# pinoccio-4x1a-motor.net
KiCad netlist of a schematic drawn in EAGLE
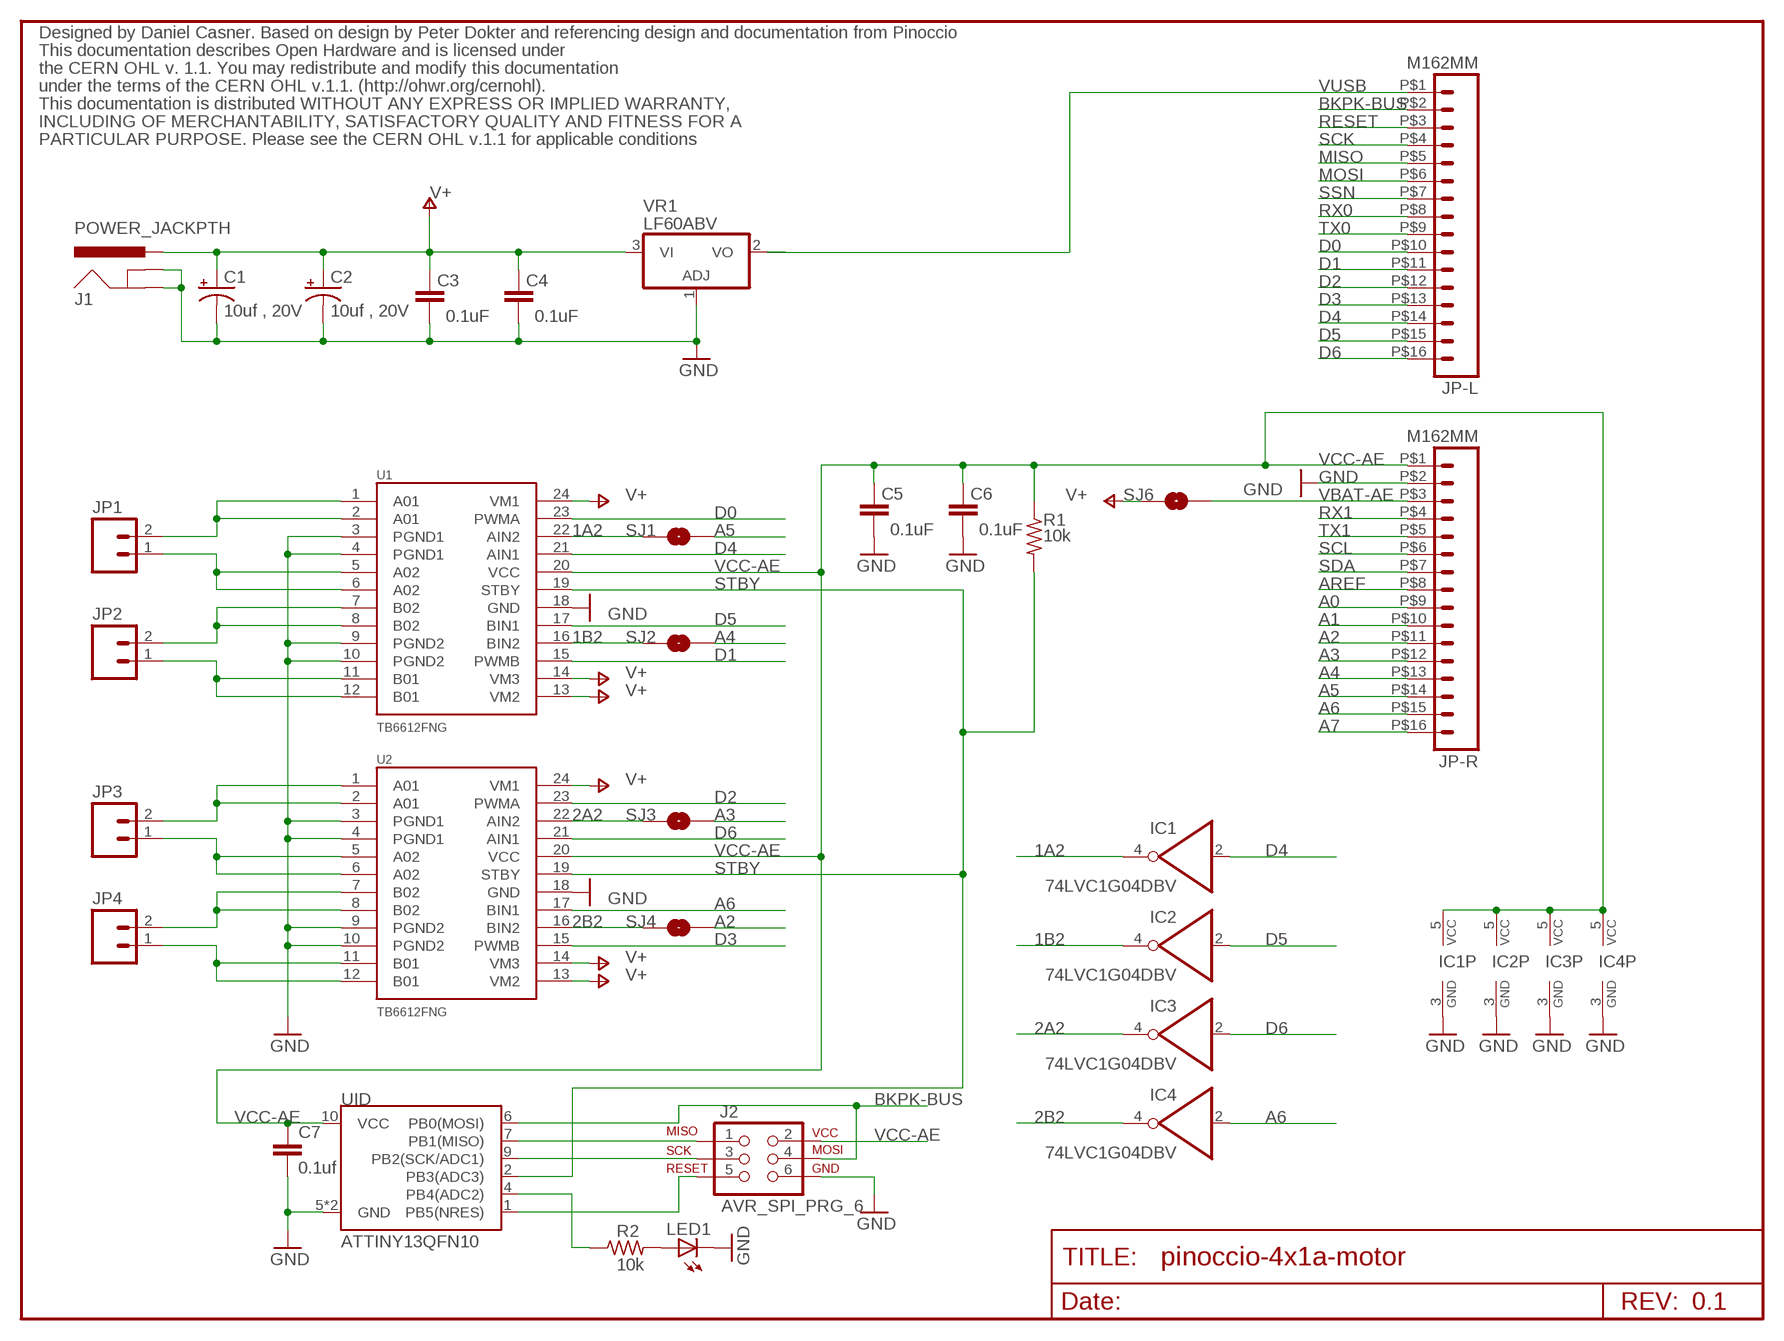
[diagram p0: schematic, sheet 1]

(export (version "E")
  (design (tool "Eeschema 10.0.6"))
  (components
    (comp (ref "C1")
      (value "10uf , 20V")
      (footprint "eagle-import:EIA3528")
      (libsource (lib "eagle-import") (part "CAP_POL3528"))
    )
    (comp (ref "C2")
      (value "10uf , 20V")
      (footprint "eagle-import:EIA3528")
      (libsource (lib "eagle-import") (part "CAP_POL3528"))
    )
    (comp (ref "C3")
      (value "0.1uF")
      (footprint "eagle-import:0402-CAP")
      (libsource (lib "eagle-import") (part "SparkFun_CAP0402-CAP"))
    )
    (comp (ref "C4")
      (value "0.1uF")
      (footprint "eagle-import:0402-CAP")
      (libsource (lib "eagle-import") (part "SparkFun_CAP0402-CAP"))
    )
    (comp (ref "C5")
      (value "0.1uF")
      (footprint "eagle-import:0402-CAP")
      (libsource (lib "eagle-import") (part "SparkFun_CAP0402-CAP"))
    )
    (comp (ref "C6")
      (value "0.1uF")
      (footprint "eagle-import:0402-CAP")
      (libsource (lib "eagle-import") (part "SparkFun_CAP0402-CAP"))
    )
    (comp (ref "C7")
      (value "0.1uf")
      (footprint "eagle-import:0402-CAP")
      (libsource (lib "eagle-import") (part "CAP0402-CAP"))
    )
    (comp (ref "IC1")
      (value "74LVC1G04DBV")
      (footprint "eagle-import:SOT23-5")
      (libsource (lib "eagle-import") (part "741G04DBVLVC"))
    )
    (comp (ref "IC2")
      (value "74LVC1G04DBV")
      (footprint "eagle-import:SOT23-5")
      (libsource (lib "eagle-import") (part "741G04DBVLVC"))
    )
    (comp (ref "IC3")
      (value "74LVC1G04DBV")
      (footprint "eagle-import:SOT23-5")
      (libsource (lib "eagle-import") (part "741G04DBVLVC"))
    )
    (comp (ref "IC4")
      (value "74LVC1G04DBV")
      (footprint "eagle-import:SOT23-5")
      (libsource (lib "eagle-import") (part "741G04DBVLVC"))
    )
    (comp (ref "J1")
      (value "POWER_JACKPTH")
      (footprint "eagle-import:POWER_JACK_PTH")
      (libsource (lib "eagle-import") (part "POWER_JACKPTH"))
    )
    (comp (ref "J2")
      (value "AVR_SPI_PRG_6")
      (footprint "eagle-import:2X3-PAD")
      (libsource (lib "eagle-import") (part "AVR_SPI_PRG_6"))
    )
    (comp (ref "JP-L")
      (value "M162MM")
      (footprint "eagle-import:1X16_2MM")
      (libsource (lib "eagle-import") (part "M162MM"))
    )
    (comp (ref "JP-R")
      (value "M162MM")
      (footprint "eagle-import:1X16_2MM")
      (libsource (lib "eagle-import") (part "M162MM"))
    )
    (comp (ref "JP1")
      (value "M02LOCK_LONGPADS")
      (footprint "eagle-import:1X02_LOCK_LONGPADS")
      (libsource (lib "eagle-import") (part "M02LOCK_LONGPADS"))
    )
    (comp (ref "JP2")
      (value "M02LOCK_LONGPADS")
      (footprint "eagle-import:1X02_LOCK_LONGPADS")
      (libsource (lib "eagle-import") (part "M02LOCK_LONGPADS"))
    )
    (comp (ref "JP3")
      (value "M02LOCK_LONGPADS")
      (footprint "eagle-import:1X02_LOCK_LONGPADS")
      (libsource (lib "eagle-import") (part "M02LOCK_LONGPADS"))
    )
    (comp (ref "JP4")
      (value "M02LOCK_LONGPADS")
      (footprint "eagle-import:1X02_LOCK_LONGPADS")
      (libsource (lib "eagle-import") (part "M02LOCK_LONGPADS"))
    )
    (comp (ref "LED1")
      (value "LED0603")
      (footprint "eagle-import:LED-0603")
      (libsource (lib "eagle-import") (part "LED0603"))
    )
    (comp (ref "R1")
      (value "10k")
      (footprint "eagle-import:R0402")
      (libsource (lib "eagle-import") (part "R-US_R0402"))
    )
    (comp (ref "R2")
      (value "10k")
      (footprint "eagle-import:R0402")
      (libsource (lib "eagle-import") (part "R-US_R0402"))
    )
    (comp (ref "SJ1")
      (value "SOLDERJUMPERNC2")
      (footprint "eagle-import:SJ_2S-NOTRACE")
      (libsource (lib "eagle-import") (part "SOLDERJUMPERNC2"))
    )
    (comp (ref "SJ2")
      (value "SOLDERJUMPERNC2")
      (footprint "eagle-import:SJ_2S-NOTRACE")
      (libsource (lib "eagle-import") (part "SOLDERJUMPERNC2"))
    )
    (comp (ref "SJ3")
      (value "SOLDERJUMPERNC2")
      (footprint "eagle-import:SJ_2S-NOTRACE")
      (libsource (lib "eagle-import") (part "SOLDERJUMPERNC2"))
    )
    (comp (ref "SJ4")
      (value "SOLDERJUMPERNC2")
      (footprint "eagle-import:SJ_2S-NOTRACE")
      (libsource (lib "eagle-import") (part "SOLDERJUMPERNC2"))
    )
    (comp (ref "SJ6")
      (value "SOLDERJUMPERNC2")
      (footprint "eagle-import:SJ_2S-NOTRACE")
      (libsource (lib "eagle-import") (part "SOLDERJUMPERNC2"))
    )
    (comp (ref "U1")
      (value "TB6612FNG")
      (footprint "eagle-import:SSOP24")
      (libsource (lib "eagle-import") (part "TB6621FNG"))
    )
    (comp (ref "U2")
      (value "TB6612FNG")
      (footprint "eagle-import:SSOP24")
      (libsource (lib "eagle-import") (part "TB6621FNG"))
    )
    (comp (ref "UID")
      (value "ATTINY13QFN10")
      (footprint "eagle-import:QFN-10")
      (libsource (lib "eagle-import") (part "ATTINY13QFN10"))
    )
    (comp (ref "VR1")
      (value "LF60ABV")
      (footprint "eagle-import:TO220H")
      (libsource (lib "eagle-import") (part "317T"))
    )
  )
  (nets
    (net (code "1") (name "/1A2") (class "Default")
      (node (ref "IC1") (pin "4") (pinfunction "O_4") (pintype "output"))
      (node (ref "SJ1") (pin "1") (pinfunction "1_1") (pintype "passive"))
      (node (ref "U1") (pin "22") (pinfunction "AIN2_22") (pintype "bidirectional"))
    )
    (net (code "2") (name "/1B2") (class "Default")
      (node (ref "IC2") (pin "4") (pinfunction "O_4") (pintype "output"))
      (node (ref "SJ2") (pin "1") (pinfunction "1_1") (pintype "passive"))
      (node (ref "U1") (pin "16") (pinfunction "BIN2_16") (pintype "bidirectional"))
    )
    (net (code "3") (name "/2A2") (class "Default")
      (node (ref "IC3") (pin "4") (pinfunction "O_4") (pintype "output"))
      (node (ref "SJ3") (pin "1") (pinfunction "1_1") (pintype "passive"))
      (node (ref "U2") (pin "22") (pinfunction "AIN2_22") (pintype "bidirectional"))
    )
    (net (code "4") (name "/2B2") (class "Default")
      (node (ref "IC4") (pin "4") (pinfunction "O_4") (pintype "output"))
      (node (ref "SJ4") (pin "1") (pinfunction "1_1") (pintype "passive"))
      (node (ref "U2") (pin "16") (pinfunction "BIN2_16") (pintype "bidirectional"))
    )
    (net (code "5") (name "/A0") (class "Default")
      (node (ref "JP-R") (pin "P$9") (pinfunction "9_P$9") (pintype "passive"))
    )
    (net (code "6") (name "/A1") (class "Default")
      (node (ref "JP-R") (pin "P$10") (pinfunction "10_P$10") (pintype "passive"))
    )
    (net (code "7") (name "/A2") (class "Default")
      (node (ref "JP-R") (pin "P$11") (pinfunction "11_P$11") (pintype "passive"))
      (node (ref "SJ4") (pin "2") (pinfunction "2_2") (pintype "passive"))
    )
    (net (code "8") (name "/A3") (class "Default")
      (node (ref "JP-R") (pin "P$12") (pinfunction "12_P$12") (pintype "passive"))
      (node (ref "SJ3") (pin "2") (pinfunction "2_2") (pintype "passive"))
    )
    (net (code "9") (name "/A4") (class "Default")
      (node (ref "JP-R") (pin "P$13") (pinfunction "13_P$13") (pintype "passive"))
      (node (ref "SJ2") (pin "2") (pinfunction "2_2") (pintype "passive"))
    )
    (net (code "10") (name "/A5") (class "Default")
      (node (ref "JP-R") (pin "P$14") (pinfunction "14_P$14") (pintype "passive"))
      (node (ref "SJ1") (pin "2") (pinfunction "2_2") (pintype "passive"))
    )
    (net (code "11") (name "/A6") (class "Default")
      (node (ref "IC4") (pin "2") (pinfunction "I_2") (pintype "input"))
      (node (ref "JP-R") (pin "P$15") (pinfunction "15_P$15") (pintype "passive"))
      (node (ref "U2") (pin "17") (pinfunction "BIN1_17") (pintype "bidirectional"))
    )
    (net (code "12") (name "/A7") (class "Default")
      (node (ref "JP-R") (pin "P$16") (pinfunction "16_P$16") (pintype "passive"))
    )
    (net (code "13") (name "/AREF") (class "Default")
      (node (ref "JP-R") (pin "P$8") (pinfunction "8_P$8") (pintype "passive"))
    )
    (net (code "14") (name "/BKPK-BUS") (class "Default")
      (node (ref "J2") (pin "4") (pinfunction "4_4") (pintype "passive"))
      (node (ref "JP-L") (pin "P$2") (pinfunction "2_P$2") (pintype "passive"))
      (node (ref "UID") (pin "6") (pinfunction "PB0(MOSI)_6") (pintype "bidirectional"))
    )
    (net (code "15") (name "/D0") (class "Default")
      (node (ref "JP-L") (pin "P$10") (pinfunction "10_P$10") (pintype "passive"))
      (node (ref "U1") (pin "23") (pinfunction "PWMA_23") (pintype "bidirectional"))
    )
    (net (code "16") (name "/D1") (class "Default")
      (node (ref "JP-L") (pin "P$11") (pinfunction "11_P$11") (pintype "passive"))
      (node (ref "U1") (pin "15") (pinfunction "PWMB_15") (pintype "bidirectional"))
    )
    (net (code "17") (name "/D2") (class "Default")
      (node (ref "JP-L") (pin "P$12") (pinfunction "12_P$12") (pintype "passive"))
      (node (ref "U2") (pin "23") (pinfunction "PWMA_23") (pintype "bidirectional"))
    )
    (net (code "18") (name "/D3") (class "Default")
      (node (ref "JP-L") (pin "P$13") (pinfunction "13_P$13") (pintype "passive"))
      (node (ref "U2") (pin "15") (pinfunction "PWMB_15") (pintype "bidirectional"))
    )
    (net (code "19") (name "/D4") (class "Default")
      (node (ref "IC1") (pin "2") (pinfunction "I_2") (pintype "input"))
      (node (ref "JP-L") (pin "P$14") (pinfunction "14_P$14") (pintype "passive"))
      (node (ref "U1") (pin "21") (pinfunction "AIN1_21") (pintype "bidirectional"))
    )
    (net (code "20") (name "/D5") (class "Default")
      (node (ref "IC2") (pin "2") (pinfunction "I_2") (pintype "input"))
      (node (ref "JP-L") (pin "P$15") (pinfunction "15_P$15") (pintype "passive"))
      (node (ref "U1") (pin "17") (pinfunction "BIN1_17") (pintype "bidirectional"))
    )
    (net (code "21") (name "/D6") (class "Default")
      (node (ref "IC3") (pin "2") (pinfunction "I_2") (pintype "input"))
      (node (ref "JP-L") (pin "P$16") (pinfunction "16_P$16") (pintype "passive"))
      (node (ref "U2") (pin "21") (pinfunction "AIN1_21") (pintype "bidirectional"))
    )
    (net (code "22") (name "/MISO") (class "Default")
      (node (ref "JP-L") (pin "P$5") (pinfunction "5_P$5") (pintype "passive"))
    )
    (net (code "23") (name "/MOSI") (class "Default")
      (node (ref "JP-L") (pin "P$6") (pinfunction "6_P$6") (pintype "passive"))
    )
    (net (code "24") (name "/RESET") (class "Default")
      (node (ref "JP-L") (pin "P$3") (pinfunction "3_P$3") (pintype "passive"))
    )
    (net (code "25") (name "/RX0") (class "Default")
      (node (ref "JP-L") (pin "P$8") (pinfunction "8_P$8") (pintype "passive"))
    )
    (net (code "26") (name "/RX1") (class "Default")
      (node (ref "JP-R") (pin "P$4") (pinfunction "4_P$4") (pintype "passive"))
    )
    (net (code "27") (name "/SCK") (class "Default")
      (node (ref "JP-L") (pin "P$4") (pinfunction "4_P$4") (pintype "passive"))
    )
    (net (code "28") (name "/SCL") (class "Default")
      (node (ref "JP-R") (pin "P$6") (pinfunction "6_P$6") (pintype "passive"))
    )
    (net (code "29") (name "/SDA") (class "Default")
      (node (ref "JP-R") (pin "P$7") (pinfunction "7_P$7") (pintype "passive"))
    )
    (net (code "30") (name "/SSN") (class "Default")
      (node (ref "JP-L") (pin "P$7") (pinfunction "7_P$7") (pintype "passive"))
    )
    (net (code "31") (name "/STBY") (class "Default")
      (node (ref "R1") (pin "2") (pinfunction "2_2") (pintype "passive"))
      (node (ref "U1") (pin "19") (pinfunction "STBY_19") (pintype "bidirectional"))
      (node (ref "U2") (pin "19") (pinfunction "STBY_19") (pintype "bidirectional"))
      (node (ref "UID") (pin "2") (pinfunction "PB3(ADC3)_2") (pintype "bidirectional"))
    )
    (net (code "32") (name "/TX0") (class "Default")
      (node (ref "JP-L") (pin "P$9") (pinfunction "9_P$9") (pintype "passive"))
    )
    (net (code "33") (name "/TX1") (class "Default")
      (node (ref "JP-R") (pin "P$5") (pinfunction "5_P$5") (pintype "passive"))
    )
    (net (code "34") (name "/VBAT-AE") (class "Default")
      (node (ref "JP-R") (pin "P$3") (pinfunction "3_P$3") (pintype "passive"))
      (node (ref "SJ6") (pin "2") (pinfunction "2_2") (pintype "passive"))
    )
    (net (code "35") (name "/VCC-AE") (class "Default")
      (node (ref "C5") (pin "2") (pinfunction "2_2") (pintype "passive"))
      (node (ref "C6") (pin "2") (pinfunction "2_2") (pintype "passive"))
      (node (ref "C7") (pin "1") (pinfunction "1_1") (pintype "passive"))
      (node (ref "IC1") (pin "5") (pinfunction "VCC_5") (pintype "power_in"))
      (node (ref "IC2") (pin "5") (pinfunction "VCC_5") (pintype "power_in"))
      (node (ref "IC3") (pin "5") (pinfunction "VCC_5") (pintype "power_in"))
      (node (ref "IC4") (pin "5") (pinfunction "VCC_5") (pintype "power_in"))
      (node (ref "J2") (pin "2") (pinfunction "2_2") (pintype "passive"))
      (node (ref "JP-R") (pin "P$1") (pinfunction "1_P$1") (pintype "passive"))
      (node (ref "R1") (pin "1") (pinfunction "1_1") (pintype "passive"))
      (node (ref "U1") (pin "20") (pinfunction "VCC_20") (pintype "bidirectional"))
      (node (ref "U2") (pin "20") (pinfunction "VCC_20") (pintype "bidirectional"))
      (node (ref "UID") (pin "10") (pinfunction "VCC_10") (pintype "bidirectional"))
    )
    (net (code "36") (name "/VUSB") (class "Default")
      (node (ref "JP-L") (pin "P$1") (pinfunction "1_P$1") (pintype "passive"))
      (node (ref "VR1") (pin "2") (pinfunction "VO_2") (pintype "passive"))
    )
    (net (code "37") (name "GND") (class "Default")
      (node (ref "C1") (pin "C") (pinfunction "-_C") (pintype "passive"))
      (node (ref "C2") (pin "C") (pinfunction "-_C") (pintype "passive"))
      (node (ref "C3") (pin "1") (pinfunction "1_1") (pintype "passive"))
      (node (ref "C4") (pin "1") (pinfunction "1_1") (pintype "passive"))
      (node (ref "C5") (pin "1") (pinfunction "1_1") (pintype "passive"))
      (node (ref "C6") (pin "1") (pinfunction "1_1") (pintype "passive"))
      (node (ref "C7") (pin "2") (pinfunction "2_2") (pintype "passive"))
      (node (ref "IC1") (pin "3") (pinfunction "GND_3") (pintype "power_in"))
      (node (ref "IC2") (pin "3") (pinfunction "GND_3") (pintype "power_in"))
      (node (ref "IC3") (pin "3") (pinfunction "GND_3") (pintype "power_in"))
      (node (ref "IC4") (pin "3") (pinfunction "GND_3") (pintype "power_in"))
      (node (ref "J1") (pin "GND") (pinfunction "GND_GND") (pintype "bidirectional"))
      (node (ref "J1") (pin "GNDBREAK") (pinfunction "GNDBREAK_GNDBREAK") (pintype "bidirectional"))
      (node (ref "J2") (pin "6") (pinfunction "6_6") (pintype "passive"))
      (node (ref "JP-R") (pin "P$2") (pinfunction "2_P$2") (pintype "passive"))
      (node (ref "LED1") (pin "C") (pinfunction "C_C") (pintype "passive"))
      (node (ref "U1") (pin "10") (pinfunction "PGND2_10") (pintype "bidirectional"))
      (node (ref "U1") (pin "18") (pinfunction "GND_18") (pintype "bidirectional"))
      (node (ref "U1") (pin "3") (pinfunction "PGND1_3") (pintype "bidirectional"))
      (node (ref "U1") (pin "4") (pinfunction "PGND1_4") (pintype "bidirectional"))
      (node (ref "U1") (pin "9") (pinfunction "PGND2_9") (pintype "bidirectional"))
      (node (ref "U2") (pin "10") (pinfunction "PGND2_10") (pintype "bidirectional"))
      (node (ref "U2") (pin "18") (pinfunction "GND_18") (pintype "bidirectional"))
      (node (ref "U2") (pin "3") (pinfunction "PGND1_3") (pintype "bidirectional"))
      (node (ref "U2") (pin "4") (pinfunction "PGND1_4") (pintype "bidirectional"))
      (node (ref "U2") (pin "9") (pinfunction "PGND2_9") (pintype "bidirectional"))
      (node (ref "UID") (pin "5") (pinfunction "GND_5") (pintype "bidirectional"))
      (node (ref "UID") (pin "EP") (pinfunction "GND_EP") (pintype "bidirectional"))
      (node (ref "VR1") (pin "1") (pinfunction "ADJ_1") (pintype "input"))
    )
    (net (code "38") (name "Net-(JP1-Pad1)") (class "Default")
      (node (ref "JP1") (pin "1") (pinfunction "1_1") (pintype "passive"))
      (node (ref "U1") (pin "5") (pinfunction "A02_5") (pintype "bidirectional"))
      (node (ref "U1") (pin "6") (pinfunction "A02_6") (pintype "bidirectional"))
    )
    (net (code "39") (name "Net-(JP1-Pad2)") (class "Default")
      (node (ref "JP1") (pin "2") (pinfunction "2_2") (pintype "passive"))
      (node (ref "U1") (pin "1") (pinfunction "A01_1") (pintype "bidirectional"))
      (node (ref "U1") (pin "2") (pinfunction "A01_2") (pintype "bidirectional"))
    )
    (net (code "40") (name "Net-(JP2-Pad1)") (class "Default")
      (node (ref "JP2") (pin "1") (pinfunction "1_1") (pintype "passive"))
      (node (ref "U1") (pin "11") (pinfunction "B01_11") (pintype "bidirectional"))
      (node (ref "U1") (pin "12") (pinfunction "B01_12") (pintype "bidirectional"))
    )
    (net (code "41") (name "Net-(JP2-Pad2)") (class "Default")
      (node (ref "JP2") (pin "2") (pinfunction "2_2") (pintype "passive"))
      (node (ref "U1") (pin "7") (pinfunction "B02_7") (pintype "bidirectional"))
      (node (ref "U1") (pin "8") (pinfunction "B02_8") (pintype "bidirectional"))
    )
    (net (code "42") (name "Net-(JP3-Pad1)") (class "Default")
      (node (ref "JP3") (pin "1") (pinfunction "1_1") (pintype "passive"))
      (node (ref "U2") (pin "5") (pinfunction "A02_5") (pintype "bidirectional"))
      (node (ref "U2") (pin "6") (pinfunction "A02_6") (pintype "bidirectional"))
    )
    (net (code "43") (name "Net-(JP3-Pad2)") (class "Default")
      (node (ref "JP3") (pin "2") (pinfunction "2_2") (pintype "passive"))
      (node (ref "U2") (pin "1") (pinfunction "A01_1") (pintype "bidirectional"))
      (node (ref "U2") (pin "2") (pinfunction "A01_2") (pintype "bidirectional"))
    )
    (net (code "44") (name "Net-(JP4-Pad1)") (class "Default")
      (node (ref "JP4") (pin "1") (pinfunction "1_1") (pintype "passive"))
      (node (ref "U2") (pin "11") (pinfunction "B01_11") (pintype "bidirectional"))
      (node (ref "U2") (pin "12") (pinfunction "B01_12") (pintype "bidirectional"))
    )
    (net (code "45") (name "Net-(JP4-Pad2)") (class "Default")
      (node (ref "JP4") (pin "2") (pinfunction "2_2") (pintype "passive"))
      (node (ref "U2") (pin "7") (pinfunction "B02_7") (pintype "bidirectional"))
      (node (ref "U2") (pin "8") (pinfunction "B02_8") (pintype "bidirectional"))
    )
    (net (code "46") (name "Net-(LED1-PadA)") (class "Default")
      (node (ref "LED1") (pin "A") (pinfunction "A_A") (pintype "passive"))
      (node (ref "R2") (pin "2") (pinfunction "2_2") (pintype "passive"))
    )
    (net (code "47") (name "Net-(UID-PB1(MISO))") (class "Default")
      (node (ref "J2") (pin "1") (pinfunction "1_1") (pintype "passive"))
      (node (ref "UID") (pin "7") (pinfunction "PB1(MISO)_7") (pintype "bidirectional"))
    )
    (net (code "48") (name "Net-(UID-PB2(SCK{slash}ADC1))") (class "Default")
      (node (ref "J2") (pin "3") (pinfunction "3_3") (pintype "passive"))
      (node (ref "UID") (pin "9") (pinfunction "PB2(SCK/ADC1)_9") (pintype "bidirectional"))
    )
    (net (code "49") (name "Net-(UID-PB4(ADC2))") (class "Default")
      (node (ref "R2") (pin "1") (pinfunction "1_1") (pintype "passive"))
      (node (ref "UID") (pin "4") (pinfunction "PB4(ADC2)_4") (pintype "bidirectional"))
    )
    (net (code "50") (name "Net-(UID-PB5(NRES))") (class "Default")
      (node (ref "J2") (pin "5") (pinfunction "5_5") (pintype "passive"))
      (node (ref "UID") (pin "1") (pinfunction "PB5(NRES)_1") (pintype "bidirectional"))
    )
    (net (code "51") (name "V+") (class "Default")
      (node (ref "C1") (pin "A") (pinfunction "+_A") (pintype "passive"))
      (node (ref "C2") (pin "A") (pinfunction "+_A") (pintype "passive"))
      (node (ref "C3") (pin "2") (pinfunction "2_2") (pintype "passive"))
      (node (ref "C4") (pin "2") (pinfunction "2_2") (pintype "passive"))
      (node (ref "J1") (pin "PWR") (pinfunction "PWR_PWR") (pintype "bidirectional"))
      (node (ref "SJ6") (pin "1") (pinfunction "1_1") (pintype "passive"))
      (node (ref "U1") (pin "13") (pinfunction "VM2_13") (pintype "bidirectional"))
      (node (ref "U1") (pin "14") (pinfunction "VM3_14") (pintype "bidirectional"))
      (node (ref "U1") (pin "24") (pinfunction "VM1_24") (pintype "bidirectional"))
      (node (ref "U2") (pin "13") (pinfunction "VM2_13") (pintype "bidirectional"))
      (node (ref "U2") (pin "14") (pinfunction "VM3_14") (pintype "bidirectional"))
      (node (ref "U2") (pin "24") (pinfunction "VM1_24") (pintype "bidirectional"))
      (node (ref "VR1") (pin "3") (pinfunction "VI_3") (pintype "input"))
    )
  )
)
